# MEMORY.net
KiCad netlist of a schematic drawn in Altium Designer
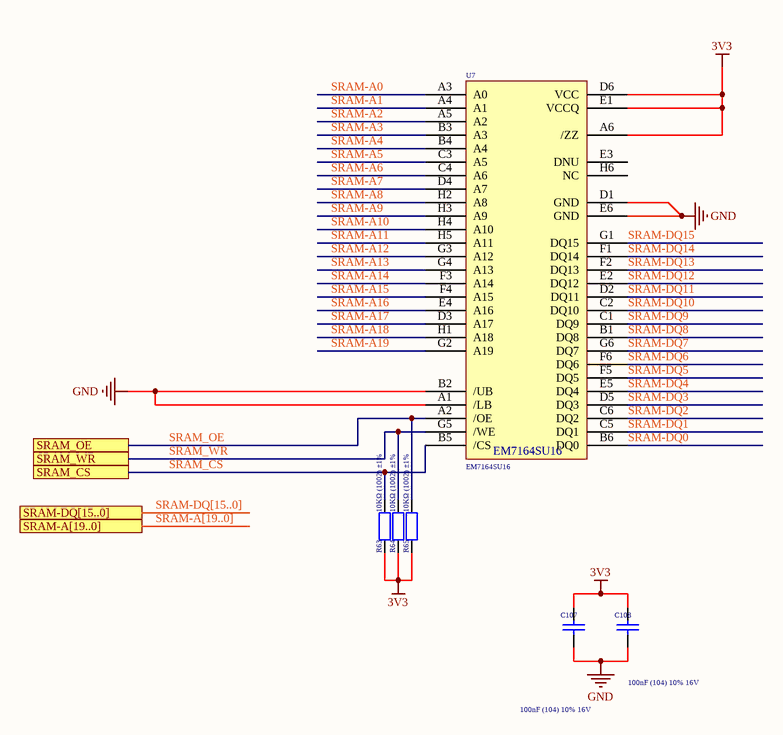
[diagram p0: MEMORY.SchDoc]

(export (version "E")
  (design (tool "Eeschema 10.0.6"))
  (components
    (comp (ref "C107")
      (value "100nF (104) 10% 16V")
      (footprint "0402_C")
      (description "贴片电容")
      (libsource (lib "Miscellaneous Devices LC") (part "0402 100nF (104) 10% 16V"))
    )
    (comp (ref "C108")
      (value "100nF (104) 10% 16V")
      (footprint "0402_C")
      (description "贴片电容")
      (libsource (lib "Miscellaneous Devices LC") (part "0402 100nF (104) 10% 16V"))
    )
    (comp (ref "R63")
      (value "10KΩ (1002) ±1%")
      (footprint "0402_R")
      (description "贴片电阻")
      (libsource (lib "Miscellaneous Devices LC") (part "0402 10KΩ (1002) 1%"))
    )
    (comp (ref "R64")
      (value "10KΩ (1002) ±1%")
      (footprint "0402_R")
      (description "贴片电阻")
      (libsource (lib "Miscellaneous Devices LC") (part "0402 10KΩ (1002) 1%"))
    )
    (comp (ref "R65")
      (value "10KΩ (1002) ±1%")
      (footprint "0402_R")
      (description "贴片电阻")
      (libsource (lib "Miscellaneous Devices LC") (part "0402 10KΩ (1002) 1%"))
    )
    (comp (ref "U7")
      (value "EM7164SU16")
      (footprint "BGA48C75P6X8_598X698X104")
      (libsource (lib "2号库") (part "EM7164SU16"))
    )
  )
  (nets
    (net (code "1") (name "/SRAM-A0") (class "Default")
      (node (ref "U7") (pin "A3") (pinfunction "A0_A3") (pintype "passive"))
    )
    (net (code "2") (name "/SRAM-A1") (class "Default")
      (node (ref "U7") (pin "A4") (pinfunction "A1_A4") (pintype "passive"))
    )
    (net (code "3") (name "/SRAM-A2") (class "Default")
      (node (ref "U7") (pin "A5") (pinfunction "A2_A5") (pintype "passive"))
    )
    (net (code "4") (name "/SRAM-A3") (class "Default")
      (node (ref "U7") (pin "B3") (pinfunction "A3_B3") (pintype "passive"))
    )
    (net (code "5") (name "/SRAM-A4") (class "Default")
      (node (ref "U7") (pin "B4") (pinfunction "A4_B4") (pintype "passive"))
    )
    (net (code "6") (name "/SRAM-A5") (class "Default")
      (node (ref "U7") (pin "C3") (pinfunction "A5_C3") (pintype "passive"))
    )
    (net (code "7") (name "/SRAM-A6") (class "Default")
      (node (ref "U7") (pin "C4") (pinfunction "A6_C4") (pintype "passive"))
    )
    (net (code "8") (name "/SRAM-A7") (class "Default")
      (node (ref "U7") (pin "D4") (pinfunction "A7_D4") (pintype "passive"))
    )
    (net (code "9") (name "/SRAM-A8") (class "Default")
      (node (ref "U7") (pin "H2") (pinfunction "A8_H2") (pintype "passive"))
    )
    (net (code "10") (name "/SRAM-A9") (class "Default")
      (node (ref "U7") (pin "H3") (pinfunction "A9_H3") (pintype "passive"))
    )
    (net (code "11") (name "/SRAM-A10") (class "Default")
      (node (ref "U7") (pin "H4") (pinfunction "A10_H4") (pintype "passive"))
    )
    (net (code "12") (name "/SRAM-A11") (class "Default")
      (node (ref "U7") (pin "H5") (pinfunction "A11_H5") (pintype "passive"))
    )
    (net (code "13") (name "/SRAM-A12") (class "Default")
      (node (ref "U7") (pin "G3") (pinfunction "A12_G3") (pintype "passive"))
    )
    (net (code "14") (name "/SRAM-A13") (class "Default")
      (node (ref "U7") (pin "G4") (pinfunction "A13_G4") (pintype "passive"))
    )
    (net (code "15") (name "/SRAM-A14") (class "Default")
      (node (ref "U7") (pin "F3") (pinfunction "A14_F3") (pintype "passive"))
    )
    (net (code "16") (name "/SRAM-A15") (class "Default")
      (node (ref "U7") (pin "F4") (pinfunction "A15_F4") (pintype "passive"))
    )
    (net (code "17") (name "/SRAM-A16") (class "Default")
      (node (ref "U7") (pin "E4") (pinfunction "A16_E4") (pintype "passive"))
    )
    (net (code "18") (name "/SRAM-A17") (class "Default")
      (node (ref "U7") (pin "D3") (pinfunction "A17_D3") (pintype "passive"))
    )
    (net (code "19") (name "/SRAM-A18") (class "Default")
      (node (ref "U7") (pin "H1") (pinfunction "A18_H1") (pintype "passive"))
    )
    (net (code "20") (name "/SRAM-A19") (class "Default")
      (node (ref "U7") (pin "G2") (pinfunction "A19_G2") (pintype "passive"))
    )
    (net (code "22") (name "/SRAM-DQ0") (class "Default")
      (node (ref "U7") (pin "B6") (pinfunction "DQ0_B6") (pintype "passive"))
    )
    (net (code "23") (name "/SRAM-DQ1") (class "Default")
      (node (ref "U7") (pin "C5") (pinfunction "DQ1_C5") (pintype "passive"))
    )
    (net (code "24") (name "/SRAM-DQ2") (class "Default")
      (node (ref "U7") (pin "C6") (pinfunction "DQ2_C6") (pintype "passive"))
    )
    (net (code "25") (name "/SRAM-DQ3") (class "Default")
      (node (ref "U7") (pin "D5") (pinfunction "DQ3_D5") (pintype "passive"))
    )
    (net (code "26") (name "/SRAM-DQ4") (class "Default")
      (node (ref "U7") (pin "E5") (pinfunction "DQ4_E5") (pintype "passive"))
    )
    (net (code "27") (name "/SRAM-DQ5") (class "Default")
      (node (ref "U7") (pin "F5") (pinfunction "DQ5_F5") (pintype "passive"))
    )
    (net (code "28") (name "/SRAM-DQ6") (class "Default")
      (node (ref "U7") (pin "F6") (pinfunction "DQ6_F6") (pintype "passive"))
    )
    (net (code "29") (name "/SRAM-DQ7") (class "Default")
      (node (ref "U7") (pin "G6") (pinfunction "DQ7_G6") (pintype "passive"))
    )
    (net (code "30") (name "/SRAM-DQ8") (class "Default")
      (node (ref "U7") (pin "B1") (pinfunction "DQ8_B1") (pintype "passive"))
    )
    (net (code "31") (name "/SRAM-DQ9") (class "Default")
      (node (ref "U7") (pin "C1") (pinfunction "DQ9_C1") (pintype "passive"))
    )
    (net (code "32") (name "/SRAM-DQ10") (class "Default")
      (node (ref "U7") (pin "C2") (pinfunction "DQ10_C2") (pintype "passive"))
    )
    (net (code "33") (name "/SRAM-DQ11") (class "Default")
      (node (ref "U7") (pin "D2") (pinfunction "DQ11_D2") (pintype "passive"))
    )
    (net (code "34") (name "/SRAM-DQ12") (class "Default")
      (node (ref "U7") (pin "E2") (pinfunction "DQ12_E2") (pintype "passive"))
    )
    (net (code "35") (name "/SRAM-DQ13") (class "Default")
      (node (ref "U7") (pin "F2") (pinfunction "DQ13_F2") (pintype "passive"))
    )
    (net (code "36") (name "/SRAM-DQ14") (class "Default")
      (node (ref "U7") (pin "F1") (pinfunction "DQ14_F1") (pintype "passive"))
    )
    (net (code "37") (name "/SRAM-DQ15") (class "Default")
      (node (ref "U7") (pin "G1") (pinfunction "DQ15_G1") (pintype "passive"))
    )
    (net (code "39") (name "/SRAM_CS") (class "Default")
      (node (ref "R63") (pin "2") (pinfunction "2_2") (pintype "passive"))
      (node (ref "U7") (pin "B5") (pinfunction "/CS_B5") (pintype "passive"))
    )
    (net (code "40") (name "/SRAM_OE") (class "Default")
      (node (ref "R65") (pin "2") (pinfunction "2_2") (pintype "passive"))
      (node (ref "U7") (pin "A2") (pinfunction "/OE_A2") (pintype "passive"))
    )
    (net (code "41") (name "/SRAM_WR") (class "Default")
      (node (ref "R64") (pin "2") (pinfunction "2_2") (pintype "passive"))
      (node (ref "U7") (pin "G5") (pinfunction "/WE_G5") (pintype "passive"))
    )
    (net (code "42") (name "3V3") (class "Default")
      (node (ref "C107") (pin "2") (pinfunction "2_2") (pintype "passive"))
      (node (ref "C108") (pin "2") (pinfunction "2_2") (pintype "passive"))
      (node (ref "R63") (pin "1") (pinfunction "1_1") (pintype "passive"))
      (node (ref "R64") (pin "1") (pinfunction "1_1") (pintype "passive"))
      (node (ref "R65") (pin "1") (pinfunction "1_1") (pintype "passive"))
      (node (ref "U7") (pin "A6") (pinfunction "/ZZ_A6") (pintype "passive"))
      (node (ref "U7") (pin "D6") (pinfunction "VCC_D6") (pintype "passive"))
      (node (ref "U7") (pin "E1") (pinfunction "VCCQ_E1") (pintype "passive"))
    )
    (net (code "43") (name "GND") (class "Default")
      (node (ref "C107") (pin "1") (pinfunction "1_1") (pintype "passive"))
      (node (ref "C108") (pin "1") (pinfunction "1_1") (pintype "passive"))
      (node (ref "U7") (pin "A1") (pinfunction "/LB_A1") (pintype "passive"))
      (node (ref "U7") (pin "B2") (pinfunction "/UB_B2") (pintype "passive"))
      (node (ref "U7") (pin "D1") (pinfunction "GND_D1") (pintype "passive"))
      (node (ref "U7") (pin "E6") (pinfunction "GND_E6") (pintype "passive"))
    )
    (net (code "44") (name "unconnected-(U7-DNU-PadE3)") (class "Default")
      (node (ref "U7") (pin "E3") (pinfunction "DNU_E3") (pintype "passive"))
    )
    (net (code "45") (name "unconnected-(U7-NC-PadH6)") (class "Default")
      (node (ref "U7") (pin "H6") (pinfunction "NC_H6") (pintype "passive"))
    )
  )
)
